# FPGA_IOs.net
KiCad netlist of a schematic drawn in Altium Designer
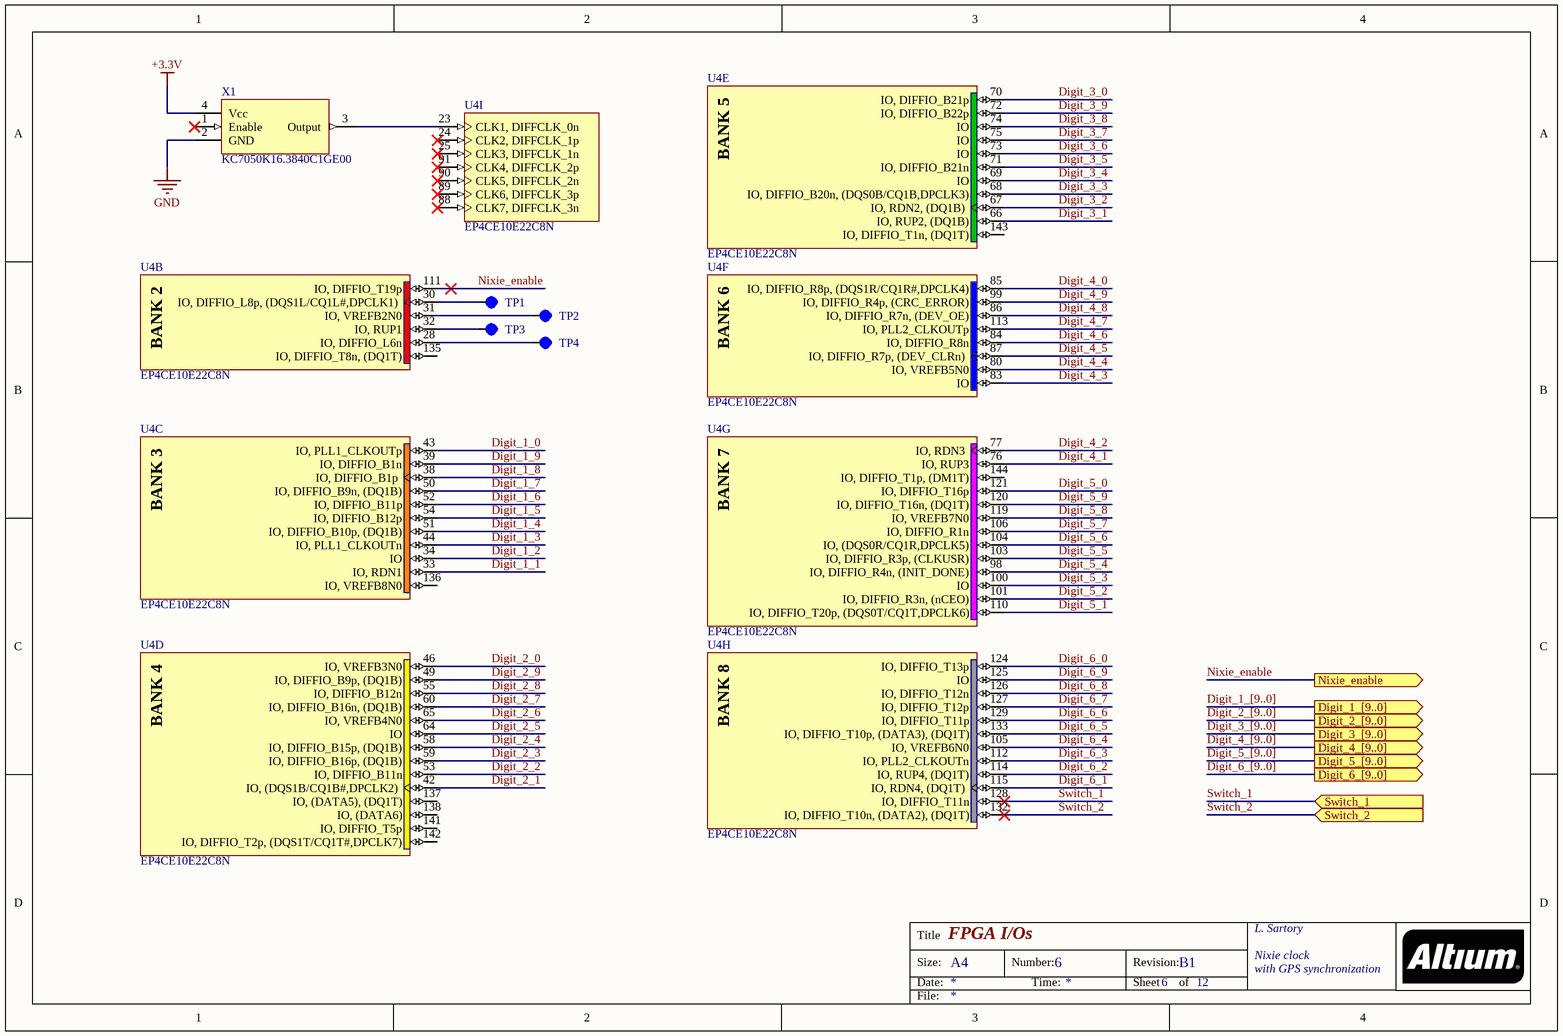
[diagram p0: FPGA_IOs.SchDoc]

(export (version "E")
  (design (tool "Eeschema 10.0.6"))
  (components
    (comp (ref "TP1")
      (value "Test_point_1mm")
      (footprint "TEST_POINT_1MM")
      (description "1mm test point")
      (libsource (lib "Nixie") (part "Test_point_1mm"))
    )
    (comp (ref "TP2")
      (value "Test_point_1mm")
      (footprint "TEST_POINT_1MM")
      (description "1mm test point")
      (libsource (lib "Nixie") (part "Test_point_1mm"))
    )
    (comp (ref "TP3")
      (value "Test_point_1mm")
      (footprint "TEST_POINT_1MM")
      (description "1mm test point")
      (libsource (lib "Nixie") (part "Test_point_1mm"))
    )
    (comp (ref "TP4")
      (value "Test_point_1mm")
      (footprint "TEST_POINT_1MM")
      (description "1mm test point")
      (libsource (lib "Nixie") (part "Test_point_1mm"))
    )
    (comp (ref "U4")
      (value "EP4CE10E22C8N")
      (footprint "EP4CE10E22C8N")
      (fields (field (name "MANUFACTURER") "Altera"))
      (libsource (lib "") (part "EP4CE10E22C8N_2"))
    )
    (comp (ref "X1")
      (value "KC7050K16.3840C1GE00")
      (footprint "KC7050K16.3840C1GE00")
      (description "Clock Oscillator, 16.384 MHz, 7x5mm")
      (libsource (lib "Nixie") (part "KC7050K16.3840C1GE00"))
    )
  )
  (nets
    (net (code "1") (name "+3.3V") (class "Default")
      (node (ref "X1") (pin "4") (pinfunction "Vcc_4") (pintype "power_in"))
    )
    (net (code "2") (name "/Digit_1_0") (class "Default")
      (node (ref "U4") (pin "43") (pinfunction "IO,_PLL1_CLKOUTp_43") (pintype "bidirectional"))
    )
    (net (code "3") (name "/Digit_1_1") (class "Default")
      (node (ref "U4") (pin "33") (pinfunction "IO,_RDN1_33") (pintype "bidirectional"))
    )
    (net (code "4") (name "/Digit_1_2") (class "Default")
      (node (ref "U4") (pin "34") (pinfunction "IO_34") (pintype "bidirectional"))
    )
    (net (code "5") (name "/Digit_1_3") (class "Default")
      (node (ref "U4") (pin "44") (pinfunction "IO,_PLL1_CLKOUTn_44") (pintype "bidirectional"))
    )
    (net (code "6") (name "/Digit_1_4") (class "Default")
      (node (ref "U4") (pin "51") (pinfunction "IO,_DIFFIO_B10p,_(DQ1B)_51") (pintype "bidirectional"))
    )
    (net (code "7") (name "/Digit_1_5") (class "Default")
      (node (ref "U4") (pin "54") (pinfunction "IO,_DIFFIO_B12p_54") (pintype "bidirectional"))
    )
    (net (code "8") (name "/Digit_1_6") (class "Default")
      (node (ref "U4") (pin "52") (pinfunction "IO,_DIFFIO_B11p_52") (pintype "bidirectional"))
    )
    (net (code "9") (name "/Digit_1_7") (class "Default")
      (node (ref "U4") (pin "50") (pinfunction "IO,_DIFFIO_B9n,_(DQ1B)_50") (pintype "bidirectional"))
    )
    (net (code "10") (name "/Digit_1_8") (class "Default")
      (node (ref "U4") (pin "38") (pinfunction "IO,_DIFFIO_B1p_38") (pintype "bidirectional"))
    )
    (net (code "11") (name "/Digit_1_9") (class "Default")
      (node (ref "U4") (pin "39") (pinfunction "IO,_DIFFIO_B1n_39") (pintype "bidirectional"))
    )
    (net (code "13") (name "/Digit_2_0") (class "Default")
      (node (ref "U4") (pin "46") (pinfunction "IO,_VREFB3N0_46") (pintype "bidirectional"))
    )
    (net (code "14") (name "/Digit_2_1") (class "Default")
      (node (ref "U4") (pin "42") (pinfunction "IO,_(DQS1B/CQ1B#,DPCLK2)_42") (pintype "bidirectional"))
    )
    (net (code "15") (name "/Digit_2_2") (class "Default")
      (node (ref "U4") (pin "53") (pinfunction "IO,_DIFFIO_B11n_53") (pintype "bidirectional"))
    )
    (net (code "16") (name "/Digit_2_3") (class "Default")
      (node (ref "U4") (pin "59") (pinfunction "IO,_DIFFIO_B16p,_(DQ1B)_59") (pintype "bidirectional"))
    )
    (net (code "17") (name "/Digit_2_4") (class "Default")
      (node (ref "U4") (pin "58") (pinfunction "IO,_DIFFIO_B15p,_(DQ1B)_58") (pintype "bidirectional"))
    )
    (net (code "18") (name "/Digit_2_5") (class "Default")
      (node (ref "U4") (pin "64") (pinfunction "IO_64") (pintype "bidirectional"))
    )
    (net (code "19") (name "/Digit_2_6") (class "Default")
      (node (ref "U4") (pin "65") (pinfunction "IO,_VREFB4N0_65") (pintype "bidirectional"))
    )
    (net (code "20") (name "/Digit_2_7") (class "Default")
      (node (ref "U4") (pin "60") (pinfunction "IO,_DIFFIO_B16n,_(DQ1B)_60") (pintype "bidirectional"))
    )
    (net (code "21") (name "/Digit_2_8") (class "Default")
      (node (ref "U4") (pin "55") (pinfunction "IO,_DIFFIO_B12n_55") (pintype "bidirectional"))
    )
    (net (code "22") (name "/Digit_2_9") (class "Default")
      (node (ref "U4") (pin "49") (pinfunction "IO,_DIFFIO_B9p,_(DQ1B)_49") (pintype "bidirectional"))
    )
    (net (code "24") (name "/Digit_3_0") (class "Default")
      (node (ref "U4") (pin "70") (pinfunction "IO,_DIFFIO_B21p_70") (pintype "bidirectional"))
    )
    (net (code "25") (name "/Digit_3_1") (class "Default")
      (node (ref "U4") (pin "66") (pinfunction "IO,_RUP2,_(DQ1B)_66") (pintype "bidirectional"))
    )
    (net (code "26") (name "/Digit_3_2") (class "Default")
      (node (ref "U4") (pin "67") (pinfunction "IO,_RDN2,_(DQ1B)_67") (pintype "bidirectional"))
    )
    (net (code "27") (name "/Digit_3_3") (class "Default")
      (node (ref "U4") (pin "68") (pinfunction "IO,_DIFFIO_B20n,_(DQS0B/CQ1B,DPCLK3)_68") (pintype "bidirectional"))
    )
    (net (code "28") (name "/Digit_3_4") (class "Default")
      (node (ref "U4") (pin "69") (pinfunction "IO_69") (pintype "bidirectional"))
    )
    (net (code "29") (name "/Digit_3_5") (class "Default")
      (node (ref "U4") (pin "71") (pinfunction "IO,_DIFFIO_B21n_71") (pintype "bidirectional"))
    )
    (net (code "30") (name "/Digit_3_6") (class "Default")
      (node (ref "U4") (pin "73") (pinfunction "IO_73") (pintype "bidirectional"))
    )
    (net (code "31") (name "/Digit_3_7") (class "Default")
      (node (ref "U4") (pin "75") (pinfunction "IO_75") (pintype "bidirectional"))
    )
    (net (code "32") (name "/Digit_3_8") (class "Default")
      (node (ref "U4") (pin "74") (pinfunction "IO_74") (pintype "bidirectional"))
    )
    (net (code "33") (name "/Digit_3_9") (class "Default")
      (node (ref "U4") (pin "72") (pinfunction "IO,_DIFFIO_B22p_72") (pintype "bidirectional"))
    )
    (net (code "35") (name "/Digit_4_0") (class "Default")
      (node (ref "U4") (pin "85") (pinfunction "IO,_DIFFIO_R8p,_(DQS1R/CQ1R#,DPCLK4)_85") (pintype "bidirectional"))
    )
    (net (code "36") (name "/Digit_4_1") (class "Default")
      (node (ref "U4") (pin "76") (pinfunction "IO,_RUP3_76") (pintype "bidirectional"))
    )
    (net (code "37") (name "/Digit_4_2") (class "Default")
      (node (ref "U4") (pin "77") (pinfunction "IO,_RDN3_77") (pintype "bidirectional"))
    )
    (net (code "38") (name "/Digit_4_3") (class "Default")
      (node (ref "U4") (pin "83") (pinfunction "IO_83") (pintype "bidirectional"))
    )
    (net (code "39") (name "/Digit_4_4") (class "Default")
      (node (ref "U4") (pin "80") (pinfunction "IO,_VREFB5N0_80") (pintype "bidirectional"))
    )
    (net (code "40") (name "/Digit_4_5") (class "Default")
      (node (ref "U4") (pin "87") (pinfunction "IO,_DIFFIO_R7p,_(DEV_CLRn)_87") (pintype "bidirectional"))
    )
    (net (code "41") (name "/Digit_4_6") (class "Default")
      (node (ref "U4") (pin "84") (pinfunction "IO,_DIFFIO_R8n_84") (pintype "bidirectional"))
    )
    (net (code "42") (name "/Digit_4_7") (class "Default")
      (node (ref "U4") (pin "113") (pinfunction "IO,_PLL2_CLKOUTp_113") (pintype "bidirectional"))
    )
    (net (code "43") (name "/Digit_4_8") (class "Default")
      (node (ref "U4") (pin "86") (pinfunction "IO,_DIFFIO_R7n,_(DEV_OE)_86") (pintype "bidirectional"))
    )
    (net (code "44") (name "/Digit_4_9") (class "Default")
      (node (ref "U4") (pin "99") (pinfunction "IO,_DIFFIO_R4p,_(CRC_ERROR)_99") (pintype "bidirectional"))
    )
    (net (code "46") (name "/Digit_5_0") (class "Default")
      (node (ref "U4") (pin "121") (pinfunction "IO,_DIFFIO_T16p_121") (pintype "bidirectional"))
    )
    (net (code "47") (name "/Digit_5_1") (class "Default")
      (node (ref "U4") (pin "110") (pinfunction "IO,_DIFFIO_T20p,_(DQS0T/CQ1T,DPCLK6)_110") (pintype "bidirectional"))
    )
    (net (code "48") (name "/Digit_5_2") (class "Default")
      (node (ref "U4") (pin "101") (pinfunction "IO,_DIFFIO_R3n,_(nCEO)_101") (pintype "bidirectional"))
    )
    (net (code "49") (name "/Digit_5_3") (class "Default")
      (node (ref "U4") (pin "100") (pinfunction "IO_100") (pintype "bidirectional"))
    )
    (net (code "50") (name "/Digit_5_4") (class "Default")
      (node (ref "U4") (pin "98") (pinfunction "IO,_DIFFIO_R4n,_(INIT_DONE)_98") (pintype "bidirectional"))
    )
    (net (code "51") (name "/Digit_5_5") (class "Default")
      (node (ref "U4") (pin "103") (pinfunction "IO,_DIFFIO_R3p,_(CLKUSR)_103") (pintype "bidirectional"))
    )
    (net (code "52") (name "/Digit_5_6") (class "Default")
      (node (ref "U4") (pin "104") (pinfunction "IO,_(DQS0R/CQ1R,DPCLK5)_104") (pintype "bidirectional"))
    )
    (net (code "53") (name "/Digit_5_7") (class "Default")
      (node (ref "U4") (pin "106") (pinfunction "IO,_DIFFIO_R1n_106") (pintype "bidirectional"))
    )
    (net (code "54") (name "/Digit_5_8") (class "Default")
      (node (ref "U4") (pin "119") (pinfunction "IO,_VREFB7N0_119") (pintype "bidirectional"))
    )
    (net (code "55") (name "/Digit_5_9") (class "Default")
      (node (ref "U4") (pin "120") (pinfunction "IO,_DIFFIO_T16n,_(DQ1T)_120") (pintype "bidirectional"))
    )
    (net (code "57") (name "/Digit_6_0") (class "Default")
      (node (ref "U4") (pin "124") (pinfunction "IO,_DIFFIO_T13p_124") (pintype "bidirectional"))
    )
    (net (code "58") (name "/Digit_6_1") (class "Default")
      (node (ref "U4") (pin "115") (pinfunction "IO,_RDN4,_(DQ1T)_115") (pintype "bidirectional"))
    )
    (net (code "59") (name "/Digit_6_2") (class "Default")
      (node (ref "U4") (pin "114") (pinfunction "IO,_RUP4,_(DQ1T)_114") (pintype "bidirectional"))
    )
    (net (code "60") (name "/Digit_6_3") (class "Default")
      (node (ref "U4") (pin "112") (pinfunction "IO,_PLL2_CLKOUTn_112") (pintype "bidirectional"))
    )
    (net (code "61") (name "/Digit_6_4") (class "Default")
      (node (ref "U4") (pin "105") (pinfunction "IO,_VREFB6N0_105") (pintype "bidirectional"))
    )
    (net (code "62") (name "/Digit_6_5") (class "Default")
      (node (ref "U4") (pin "133") (pinfunction "IO,_DIFFIO_T10p,_(DATA3),_(DQ1T)_133") (pintype "bidirectional"))
    )
    (net (code "63") (name "/Digit_6_6") (class "Default")
      (node (ref "U4") (pin "129") (pinfunction "IO,_DIFFIO_T11p_129") (pintype "bidirectional"))
    )
    (net (code "64") (name "/Digit_6_7") (class "Default")
      (node (ref "U4") (pin "127") (pinfunction "IO,_DIFFIO_T12p_127") (pintype "bidirectional"))
    )
    (net (code "65") (name "/Digit_6_8") (class "Default")
      (node (ref "U4") (pin "126") (pinfunction "IO,_DIFFIO_T12n_126") (pintype "bidirectional"))
    )
    (net (code "66") (name "/Digit_6_9") (class "Default")
      (node (ref "U4") (pin "125") (pinfunction "IO_125") (pintype "bidirectional"))
    )
    (net (code "68") (name "/Nixie_enable") (class "Default")
      (node (ref "U4") (pin "111") (pinfunction "IO,_DIFFIO_T19p_111") (pintype "bidirectional"))
    )
    (net (code "69") (name "/Switch_1") (class "Default")
      (node (ref "U4") (pin "128") (pinfunction "IO,_DIFFIO_T11n_128") (pintype "bidirectional+no_connect"))
    )
    (net (code "70") (name "/Switch_2") (class "Default")
      (node (ref "U4") (pin "132") (pinfunction "IO,_DIFFIO_T10n,_(DATA2),_(DQ1T)_132") (pintype "bidirectional+no_connect"))
    )
    (net (code "71") (name "GND") (class "Default")
      (node (ref "X1") (pin "2") (pinfunction "GND_2") (pintype "power_in"))
    )
    (net (code "72") (name "Net-(U4B-IO,_DIFFIO_L6n)") (class "Default")
      (node (ref "TP4") (pin "TP") (pinfunction "TP_TP") (pintype "passive"))
      (node (ref "U4") (pin "28") (pinfunction "IO,_DIFFIO_L6n_28") (pintype "bidirectional"))
    )
    (net (code "73") (name "Net-(U4B-IO,_DIFFIO_L8p,_(DQS1L{slash}CQ1L#,DPCLK1))") (class "Default")
      (node (ref "TP1") (pin "TP") (pinfunction "TP_TP") (pintype "passive"))
      (node (ref "U4") (pin "30") (pinfunction "IO,_DIFFIO_L8p,_(DQS1L/CQ1L#,DPCLK1)_30") (pintype "bidirectional"))
    )
    (net (code "74") (name "Net-(U4B-IO,_RUP1)") (class "Default")
      (node (ref "TP3") (pin "TP") (pinfunction "TP_TP") (pintype "passive"))
      (node (ref "U4") (pin "32") (pinfunction "IO,_RUP1_32") (pintype "bidirectional"))
    )
    (net (code "75") (name "Net-(U4B-IO,_VREFB2N0)") (class "Default")
      (node (ref "TP2") (pin "TP") (pinfunction "TP_TP") (pintype "passive"))
      (node (ref "U4") (pin "31") (pinfunction "IO,_VREFB2N0_31") (pintype "bidirectional"))
    )
    (net (code "76") (name "Net-(U4I-CLK1,_DIFFCLK_0n)") (class "Default")
      (node (ref "U4") (pin "23") (pinfunction "CLK1,_DIFFCLK_0n_23") (pintype "input"))
      (node (ref "X1") (pin "3") (pinfunction "Output_3") (pintype "output"))
    )
    (net (code "77") (name "unconnected-(U4B-IO,_DIFFIO_T8n,_(DQ1T)-Pad135)") (class "Default")
      (node (ref "U4") (pin "135") (pinfunction "IO,_DIFFIO_T8n,_(DQ1T)_135") (pintype "bidirectional"))
    )
    (net (code "78") (name "unconnected-(U4C-IO,_VREFB8N0-Pad136)") (class "Default")
      (node (ref "U4") (pin "136") (pinfunction "IO,_VREFB8N0_136") (pintype "bidirectional"))
    )
    (net (code "79") (name "unconnected-(U4D-IO,_(DATA5),_(DQ1T)-Pad137)") (class "Default")
      (node (ref "U4") (pin "137") (pinfunction "IO,_(DATA5),_(DQ1T)_137") (pintype "bidirectional"))
    )
    (net (code "80") (name "unconnected-(U4D-IO,_(DATA6)-Pad138)") (class "Default")
      (node (ref "U4") (pin "138") (pinfunction "IO,_(DATA6)_138") (pintype "bidirectional"))
    )
    (net (code "81") (name "unconnected-(U4D-IO,_DIFFIO_T2p,_(DQS1T{slash}CQ1T#,DPCLK7)-Pad142)") (class "Default")
      (node (ref "U4") (pin "142") (pinfunction "IO,_DIFFIO_T2p,_(DQS1T/CQ1T#,DPCLK7)_142") (pintype "bidirectional"))
    )
    (net (code "82") (name "unconnected-(U4D-IO,_DIFFIO_T5p-Pad141)") (class "Default")
      (node (ref "U4") (pin "141") (pinfunction "IO,_DIFFIO_T5p_141") (pintype "bidirectional"))
    )
    (net (code "83") (name "unconnected-(U4E-IO,_DIFFIO_T1n,_(DQ1T)-Pad143)") (class "Default")
      (node (ref "U4") (pin "143") (pinfunction "IO,_DIFFIO_T1n,_(DQ1T)_143") (pintype "bidirectional"))
    )
    (net (code "84") (name "unconnected-(U4G-IO,_DIFFIO_T1p,_(DM1T)-Pad144)") (class "Default")
      (node (ref "U4") (pin "144") (pinfunction "IO,_DIFFIO_T1p,_(DM1T)_144") (pintype "bidirectional"))
    )
    (net (code "85") (name "unconnected-(U4I-CLK2,_DIFFCLK_1p-Pad24)") (class "Default")
      (node (ref "U4") (pin "24") (pinfunction "CLK2,_DIFFCLK_1p_24") (pintype "input+no_connect"))
    )
    (net (code "86") (name "unconnected-(U4I-CLK3,_DIFFCLK_1n-Pad25)") (class "Default")
      (node (ref "U4") (pin "25") (pinfunction "CLK3,_DIFFCLK_1n_25") (pintype "input+no_connect"))
    )
    (net (code "87") (name "unconnected-(U4I-CLK4,_DIFFCLK_2p-Pad91)") (class "Default")
      (node (ref "U4") (pin "91") (pinfunction "CLK4,_DIFFCLK_2p_91") (pintype "input+no_connect"))
    )
    (net (code "88") (name "unconnected-(U4I-CLK5,_DIFFCLK_2n-Pad90)") (class "Default")
      (node (ref "U4") (pin "90") (pinfunction "CLK5,_DIFFCLK_2n_90") (pintype "input+no_connect"))
    )
    (net (code "89") (name "unconnected-(U4I-CLK6,_DIFFCLK_3p-Pad89)") (class "Default")
      (node (ref "U4") (pin "89") (pinfunction "CLK6,_DIFFCLK_3p_89") (pintype "input+no_connect"))
    )
    (net (code "90") (name "unconnected-(U4I-CLK7,_DIFFCLK_3n-Pad88)") (class "Default")
      (node (ref "U4") (pin "88") (pinfunction "CLK7,_DIFFCLK_3n_88") (pintype "input+no_connect"))
    )
    (net (code "91") (name "unconnected-(X1-Enable-Pad1)") (class "Default")
      (node (ref "X1") (pin "1") (pinfunction "Enable_1") (pintype "input+no_connect"))
    )
  )
)
